# untitled.net
KiCad netlist of a schematic drawn in EAGLE
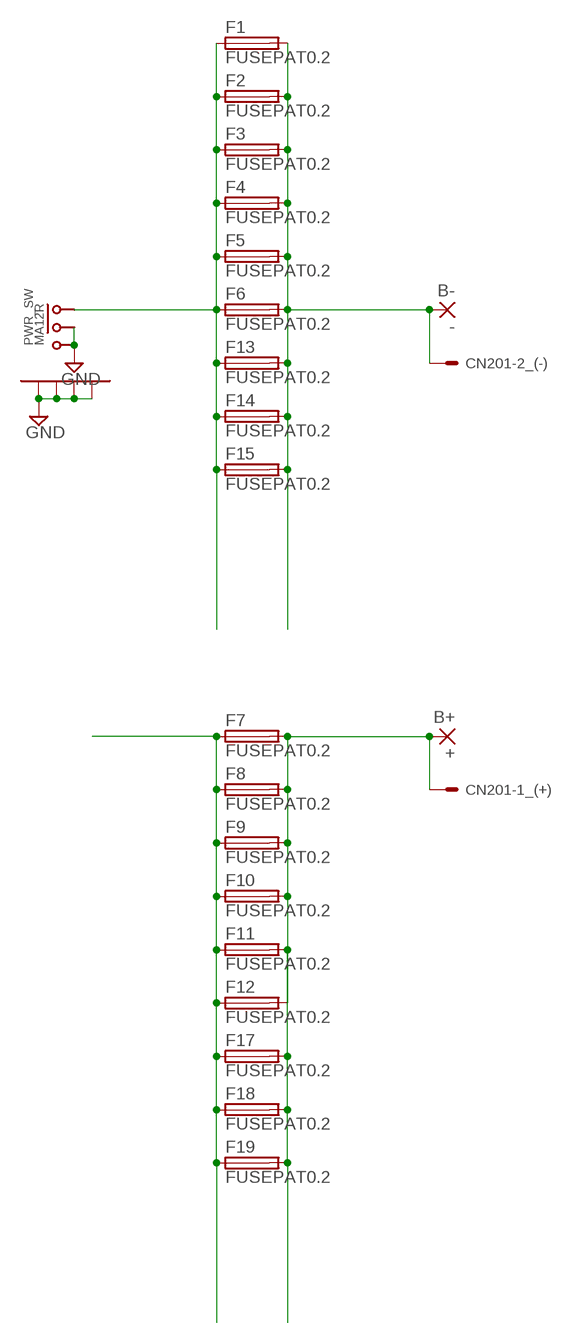
[diagram p0: schematic, sheet 1]

(export (version "E")
  (design (tool "Eeschema 10.0.6"))
  (components
    (comp (ref "B+")
      (value "+")
      (footprint "eagle-import:SMD2,5-5")
      (libsource (lib "eagle-import") (part "PAD2.5-5"))
    )
    (comp (ref "B-")
      (value "-")
      (footprint "eagle-import:SMD2,5-5")
      (libsource (lib "eagle-import") (part "PAD2.5-5"))
    )
    (comp (ref "CN201")
      (value "2P_(POWER)53048")
      (footprint "eagle-import:53048-0210")
      (libsource (lib "eagle-import") (part "2P_(POWER)53048"))
    )
    (comp (ref "F1")
      (value "FUSEPAT0.2")
      (footprint "eagle-import:FUSE_PAT1")
      (libsource (lib "eagle-import") (part "FUSEPAT0.2"))
    )
    (comp (ref "F2")
      (value "FUSEPAT0.2")
      (footprint "eagle-import:FUSE_PAT1")
      (libsource (lib "eagle-import") (part "FUSEPAT0.2"))
    )
    (comp (ref "F3")
      (value "FUSEPAT0.2")
      (footprint "eagle-import:FUSE_PAT1")
      (libsource (lib "eagle-import") (part "FUSEPAT0.2"))
    )
    (comp (ref "F4")
      (value "FUSEPAT0.2")
      (footprint "eagle-import:FUSE_PAT1")
      (libsource (lib "eagle-import") (part "FUSEPAT0.2"))
    )
    (comp (ref "F5")
      (value "FUSEPAT0.2")
      (footprint "eagle-import:FUSE_PAT1")
      (libsource (lib "eagle-import") (part "FUSEPAT0.2"))
    )
    (comp (ref "F6")
      (value "FUSEPAT0.2")
      (footprint "eagle-import:FUSE_PAT1")
      (libsource (lib "eagle-import") (part "FUSEPAT0.2"))
    )
    (comp (ref "F7")
      (value "FUSEPAT0.2")
      (footprint "eagle-import:FUSE_PAT1")
      (libsource (lib "eagle-import") (part "FUSEPAT0.2"))
    )
    (comp (ref "F8")
      (value "FUSEPAT0.2")
      (footprint "eagle-import:FUSE_PAT1")
      (libsource (lib "eagle-import") (part "FUSEPAT0.2"))
    )
    (comp (ref "F9")
      (value "FUSEPAT0.2")
      (footprint "eagle-import:FUSE_PAT1")
      (libsource (lib "eagle-import") (part "FUSEPAT0.2"))
    )
    (comp (ref "F10")
      (value "FUSEPAT0.2")
      (footprint "eagle-import:FUSE_PAT1")
      (libsource (lib "eagle-import") (part "FUSEPAT0.2"))
    )
    (comp (ref "F11")
      (value "FUSEPAT0.2")
      (footprint "eagle-import:FUSE_PAT1")
      (libsource (lib "eagle-import") (part "FUSEPAT0.2"))
    )
    (comp (ref "F12")
      (value "FUSEPAT0.2")
      (footprint "eagle-import:FUSE_PAT1")
      (libsource (lib "eagle-import") (part "FUSEPAT0.2"))
    )
    (comp (ref "F13")
      (value "FUSEPAT0.2")
      (footprint "eagle-import:FUSE_PAT1")
      (libsource (lib "eagle-import") (part "FUSEPAT0.2"))
    )
    (comp (ref "F14")
      (value "FUSEPAT0.2")
      (footprint "eagle-import:FUSE_PAT1")
      (libsource (lib "eagle-import") (part "FUSEPAT0.2"))
    )
    (comp (ref "F15")
      (value "FUSEPAT0.2")
      (footprint "eagle-import:FUSE_PAT1")
      (libsource (lib "eagle-import") (part "FUSEPAT0.2"))
    )
    (comp (ref "F17")
      (value "FUSEPAT0.2")
      (footprint "eagle-import:FUSE_PAT1")
      (libsource (lib "eagle-import") (part "FUSEPAT0.2"))
    )
    (comp (ref "F18")
      (value "FUSEPAT0.2")
      (footprint "eagle-import:FUSE_PAT1")
      (libsource (lib "eagle-import") (part "FUSEPAT0.2"))
    )
    (comp (ref "F19")
      (value "FUSEPAT0.2")
      (footprint "eagle-import:FUSE_PAT1")
      (libsource (lib "eagle-import") (part "FUSEPAT0.2"))
    )
    (comp (ref "PWR_SW")
      (value "MA12R")
      (footprint "eagle-import:MA12R")
      (libsource (lib "eagle-import") (part "MA12R"))
    )
  )
  (nets
    (net (code "1") (name "GND") (class "Default")
      (node (ref "PWR_SW") (pin "P$2") (pinfunction "2_P$2") (pintype "bidirectional"))
      (node (ref "PWR_SW") (pin "P$3") (pinfunction "3_P$3") (pintype "bidirectional"))
      (node (ref "PWR_SW") (pin "P$4") (pinfunction "P$1_P$4") (pintype "bidirectional"))
      (node (ref "PWR_SW") (pin "P$5") (pinfunction "P$2_P$5") (pintype "bidirectional"))
      (node (ref "PWR_SW") (pin "P$6") (pinfunction "P$3_P$6") (pintype "bidirectional"))
      (node (ref "PWR_SW") (pin "P$7") (pinfunction "P$4_P$7") (pintype "bidirectional"))
    )
    (net (code "2") (name "Net-(B+-P)") (class "Default")
      (node (ref "B+") (pin "1") (pinfunction "P_1") (pintype "passive"))
      (node (ref "CN201") (pin "1") (pinfunction "S_1") (pintype "passive"))
      (node (ref "F10") (pin "P$2") (pinfunction "2_P$2") (pintype "passive"))
      (node (ref "F11") (pin "P$2") (pinfunction "2_P$2") (pintype "passive"))
      (node (ref "F12") (pin "P$2") (pinfunction "2_P$2") (pintype "passive"))
      (node (ref "F17") (pin "P$2") (pinfunction "2_P$2") (pintype "passive"))
      (node (ref "F18") (pin "P$2") (pinfunction "2_P$2") (pintype "passive"))
      (node (ref "F19") (pin "P$2") (pinfunction "2_P$2") (pintype "passive"))
      (node (ref "F7") (pin "P$2") (pinfunction "2_P$2") (pintype "passive"))
      (node (ref "F8") (pin "P$2") (pinfunction "2_P$2") (pintype "passive"))
      (node (ref "F9") (pin "P$2") (pinfunction "2_P$2") (pintype "passive"))
    )
    (net (code "3") (name "Net-(B--P)") (class "Default")
      (node (ref "B-") (pin "1") (pinfunction "P_1") (pintype "passive"))
      (node (ref "CN201") (pin "2") (pinfunction "S_2") (pintype "passive"))
      (node (ref "F1") (pin "P$2") (pinfunction "2_P$2") (pintype "passive"))
      (node (ref "F13") (pin "P$2") (pinfunction "2_P$2") (pintype "passive"))
      (node (ref "F14") (pin "P$2") (pinfunction "2_P$2") (pintype "passive"))
      (node (ref "F15") (pin "P$2") (pinfunction "2_P$2") (pintype "passive"))
      (node (ref "F2") (pin "P$2") (pinfunction "2_P$2") (pintype "passive"))
      (node (ref "F3") (pin "P$2") (pinfunction "2_P$2") (pintype "passive"))
      (node (ref "F4") (pin "P$2") (pinfunction "2_P$2") (pintype "passive"))
      (node (ref "F5") (pin "P$2") (pinfunction "2_P$2") (pintype "passive"))
      (node (ref "F6") (pin "P$2") (pinfunction "2_P$2") (pintype "passive"))
    )
    (net (code "4") (name "Net-(F1-1)") (class "Default")
      (node (ref "F1") (pin "P$1") (pinfunction "1_P$1") (pintype "passive"))
      (node (ref "F13") (pin "P$1") (pinfunction "1_P$1") (pintype "passive"))
      (node (ref "F14") (pin "P$1") (pinfunction "1_P$1") (pintype "passive"))
      (node (ref "F15") (pin "P$1") (pinfunction "1_P$1") (pintype "passive"))
      (node (ref "F2") (pin "P$1") (pinfunction "1_P$1") (pintype "passive"))
      (node (ref "F3") (pin "P$1") (pinfunction "1_P$1") (pintype "passive"))
      (node (ref "F4") (pin "P$1") (pinfunction "1_P$1") (pintype "passive"))
      (node (ref "F5") (pin "P$1") (pinfunction "1_P$1") (pintype "passive"))
      (node (ref "F6") (pin "P$1") (pinfunction "1_P$1") (pintype "passive"))
      (node (ref "PWR_SW") (pin "P$1") (pinfunction "1_P$1") (pintype "bidirectional"))
    )
    (net (code "5") (name "Net-(F10-1)") (class "Default")
      (node (ref "F10") (pin "P$1") (pinfunction "1_P$1") (pintype "passive"))
      (node (ref "F11") (pin "P$1") (pinfunction "1_P$1") (pintype "passive"))
      (node (ref "F12") (pin "P$1") (pinfunction "1_P$1") (pintype "passive"))
      (node (ref "F17") (pin "P$1") (pinfunction "1_P$1") (pintype "passive"))
      (node (ref "F18") (pin "P$1") (pinfunction "1_P$1") (pintype "passive"))
      (node (ref "F19") (pin "P$1") (pinfunction "1_P$1") (pintype "passive"))
      (node (ref "F7") (pin "P$1") (pinfunction "1_P$1") (pintype "passive"))
      (node (ref "F8") (pin "P$1") (pinfunction "1_P$1") (pintype "passive"))
      (node (ref "F9") (pin "P$1") (pinfunction "1_P$1") (pintype "passive"))
    )
  )
)
